# connector_final_rev01.net
KiCad netlist of a schematic drawn in EAGLE
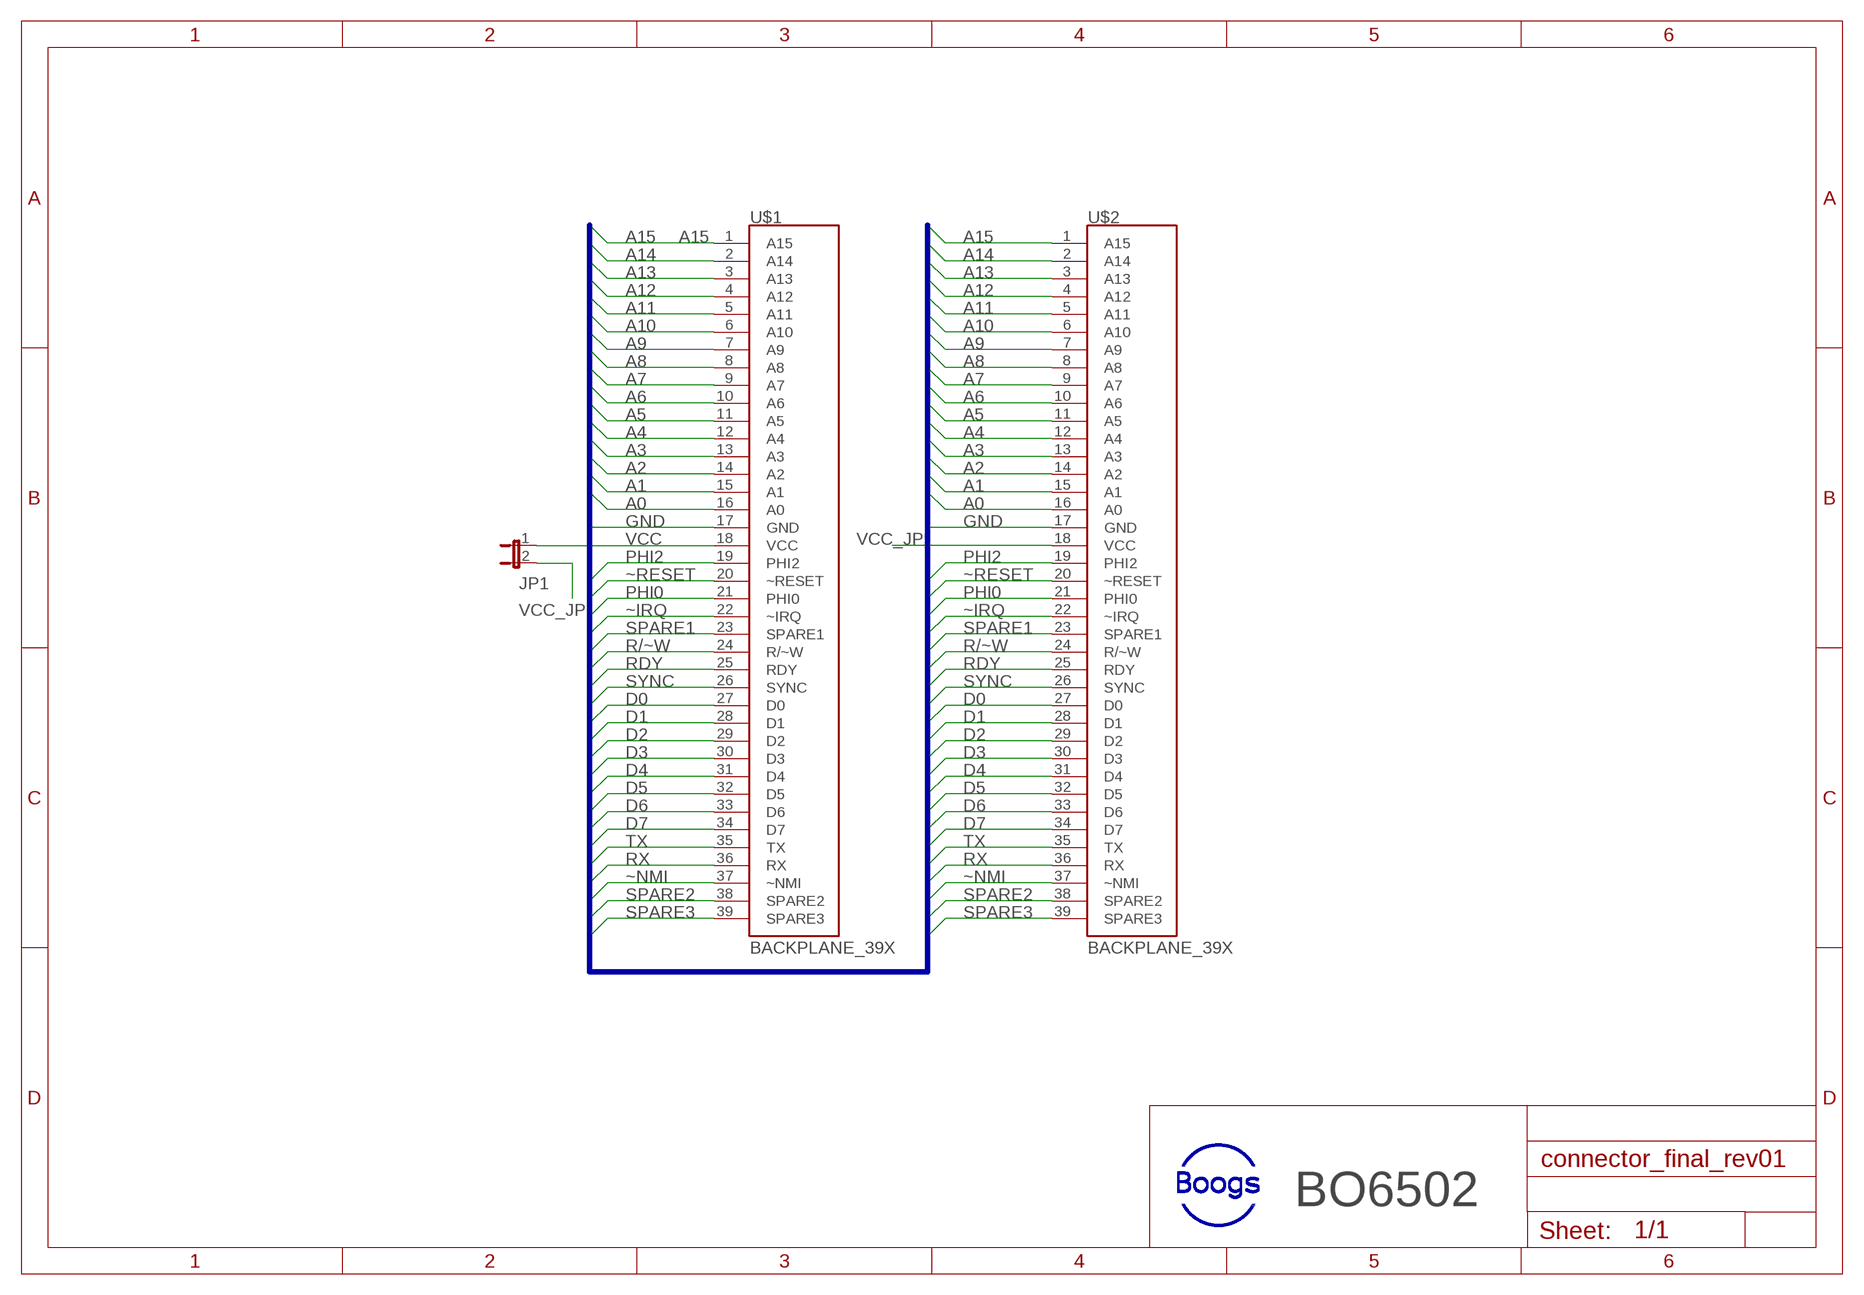
[diagram p0: schematic, sheet 1]

(export (version "E")
  (design (tool "Eeschema 10.0.6"))
  (components
    (comp (ref "JP1")
      (value "JP1E")
      (footprint "eagle-import:JP1")
      (libsource (lib "eagle-import") (part "JP1E"))
    )
    (comp (ref "U$1")
      (value "BACKPLANE_39X")
      (footprint "eagle-import:BP_39X")
      (fields (field (name "A15") "A15"))
      (libsource (lib "eagle-import") (part "BACKPLANE_39X"))
    )
    (comp (ref "U$2")
      (value "BACKPLANE_39X")
      (footprint "eagle-import:BP_39X")
      (libsource (lib "eagle-import") (part "BACKPLANE_39X"))
    )
  )
  (nets
    (net (code "1") (name "/A0") (class "Default")
      (node (ref "U$1") (pin "16") (pinfunction "A0_16") (pintype "bidirectional"))
      (node (ref "U$2") (pin "16") (pinfunction "A0_16") (pintype "bidirectional"))
    )
    (net (code "2") (name "/A1") (class "Default")
      (node (ref "U$1") (pin "15") (pinfunction "A1_15") (pintype "bidirectional"))
      (node (ref "U$2") (pin "15") (pinfunction "A1_15") (pintype "bidirectional"))
    )
    (net (code "3") (name "/A2") (class "Default")
      (node (ref "U$1") (pin "14") (pinfunction "A2_14") (pintype "bidirectional"))
      (node (ref "U$2") (pin "14") (pinfunction "A2_14") (pintype "bidirectional"))
    )
    (net (code "4") (name "/A3") (class "Default")
      (node (ref "U$1") (pin "13") (pinfunction "A3_13") (pintype "bidirectional"))
      (node (ref "U$2") (pin "13") (pinfunction "A3_13") (pintype "bidirectional"))
    )
    (net (code "5") (name "/A4") (class "Default")
      (node (ref "U$1") (pin "12") (pinfunction "A4_12") (pintype "bidirectional"))
      (node (ref "U$2") (pin "12") (pinfunction "A4_12") (pintype "bidirectional"))
    )
    (net (code "6") (name "/A5") (class "Default")
      (node (ref "U$1") (pin "11") (pinfunction "A5_11") (pintype "bidirectional"))
      (node (ref "U$2") (pin "11") (pinfunction "A5_11") (pintype "bidirectional"))
    )
    (net (code "7") (name "/A6") (class "Default")
      (node (ref "U$1") (pin "10") (pinfunction "A6_10") (pintype "bidirectional"))
      (node (ref "U$2") (pin "10") (pinfunction "A6_10") (pintype "bidirectional"))
    )
    (net (code "8") (name "/A7") (class "Default")
      (node (ref "U$1") (pin "9") (pinfunction "A7_9") (pintype "bidirectional"))
      (node (ref "U$2") (pin "9") (pinfunction "A7_9") (pintype "bidirectional"))
    )
    (net (code "9") (name "/A8") (class "Default")
      (node (ref "U$1") (pin "8") (pinfunction "A8_8") (pintype "bidirectional"))
      (node (ref "U$2") (pin "8") (pinfunction "A8_8") (pintype "bidirectional"))
    )
    (net (code "10") (name "/A9") (class "Default")
      (node (ref "U$1") (pin "7") (pinfunction "A9_7") (pintype "bidirectional"))
      (node (ref "U$2") (pin "7") (pinfunction "A9_7") (pintype "bidirectional"))
    )
    (net (code "11") (name "/A10") (class "Default")
      (node (ref "U$1") (pin "6") (pinfunction "A10_6") (pintype "bidirectional"))
      (node (ref "U$2") (pin "6") (pinfunction "A10_6") (pintype "bidirectional"))
    )
    (net (code "12") (name "/A11") (class "Default")
      (node (ref "U$1") (pin "5") (pinfunction "A11_5") (pintype "bidirectional"))
      (node (ref "U$2") (pin "5") (pinfunction "A11_5") (pintype "bidirectional"))
    )
    (net (code "13") (name "/A12") (class "Default")
      (node (ref "U$1") (pin "4") (pinfunction "A12_4") (pintype "bidirectional"))
      (node (ref "U$2") (pin "4") (pinfunction "A12_4") (pintype "bidirectional"))
    )
    (net (code "14") (name "/A13") (class "Default")
      (node (ref "U$1") (pin "3") (pinfunction "A13_3") (pintype "bidirectional"))
      (node (ref "U$2") (pin "3") (pinfunction "A13_3") (pintype "bidirectional"))
    )
    (net (code "15") (name "/A14") (class "Default")
      (node (ref "U$1") (pin "2") (pinfunction "A14_2") (pintype "bidirectional"))
      (node (ref "U$2") (pin "2") (pinfunction "A14_2") (pintype "bidirectional"))
    )
    (net (code "16") (name "/A15") (class "Default")
      (node (ref "U$1") (pin "1") (pinfunction "A15_1") (pintype "bidirectional"))
      (node (ref "U$2") (pin "1") (pinfunction "A15_1") (pintype "bidirectional"))
    )
    (net (code "17") (name "/D0") (class "Default")
      (node (ref "U$1") (pin "27") (pinfunction "D0_27") (pintype "bidirectional"))
      (node (ref "U$2") (pin "27") (pinfunction "D0_27") (pintype "bidirectional"))
    )
    (net (code "18") (name "/D1") (class "Default")
      (node (ref "U$1") (pin "28") (pinfunction "D1_28") (pintype "bidirectional"))
      (node (ref "U$2") (pin "28") (pinfunction "D1_28") (pintype "bidirectional"))
    )
    (net (code "19") (name "/D2") (class "Default")
      (node (ref "U$1") (pin "29") (pinfunction "D2_29") (pintype "bidirectional"))
      (node (ref "U$2") (pin "29") (pinfunction "D2_29") (pintype "bidirectional"))
    )
    (net (code "20") (name "/D3") (class "Default")
      (node (ref "U$1") (pin "30") (pinfunction "D3_30") (pintype "bidirectional"))
      (node (ref "U$2") (pin "30") (pinfunction "D3_30") (pintype "bidirectional"))
    )
    (net (code "21") (name "/D4") (class "Default")
      (node (ref "U$1") (pin "31") (pinfunction "D4_31") (pintype "bidirectional"))
      (node (ref "U$2") (pin "31") (pinfunction "D4_31") (pintype "bidirectional"))
    )
    (net (code "22") (name "/D5") (class "Default")
      (node (ref "U$1") (pin "32") (pinfunction "D5_32") (pintype "bidirectional"))
      (node (ref "U$2") (pin "32") (pinfunction "D5_32") (pintype "bidirectional"))
    )
    (net (code "23") (name "/D6") (class "Default")
      (node (ref "U$1") (pin "33") (pinfunction "D6_33") (pintype "bidirectional"))
      (node (ref "U$2") (pin "33") (pinfunction "D6_33") (pintype "bidirectional"))
    )
    (net (code "24") (name "/D7") (class "Default")
      (node (ref "U$1") (pin "34") (pinfunction "D7_34") (pintype "bidirectional"))
      (node (ref "U$2") (pin "34") (pinfunction "D7_34") (pintype "bidirectional"))
    )
    (net (code "25") (name "/GND") (class "Default")
      (node (ref "U$1") (pin "17") (pinfunction "GND_17") (pintype "bidirectional"))
      (node (ref "U$2") (pin "17") (pinfunction "GND_17") (pintype "bidirectional"))
    )
    (net (code "26") (name "/PHI0") (class "Default")
      (node (ref "U$1") (pin "21") (pinfunction "PHI0_21") (pintype "bidirectional"))
      (node (ref "U$2") (pin "21") (pinfunction "PHI0_21") (pintype "bidirectional"))
    )
    (net (code "27") (name "/PHI2") (class "Default")
      (node (ref "U$1") (pin "19") (pinfunction "PHI2_19") (pintype "bidirectional"))
      (node (ref "U$2") (pin "19") (pinfunction "PHI2_19") (pintype "bidirectional"))
    )
    (net (code "28") (name "/RDY") (class "Default")
      (node (ref "U$1") (pin "25") (pinfunction "RDY_25") (pintype "bidirectional"))
      (node (ref "U$2") (pin "25") (pinfunction "RDY_25") (pintype "bidirectional"))
    )
    (net (code "29") (name "/RX") (class "Default")
      (node (ref "U$1") (pin "36") (pinfunction "RX_36") (pintype "bidirectional"))
      (node (ref "U$2") (pin "36") (pinfunction "RX_36") (pintype "bidirectional"))
    )
    (net (code "30") (name "/R{slash}~{W}") (class "Default")
      (node (ref "U$1") (pin "24") (pinfunction "R/~{W}_24") (pintype "bidirectional"))
      (node (ref "U$2") (pin "24") (pinfunction "R/~{W}_24") (pintype "bidirectional"))
    )
    (net (code "31") (name "/SPARE1") (class "Default")
      (node (ref "U$1") (pin "23") (pinfunction "SPARE1_23") (pintype "bidirectional"))
      (node (ref "U$2") (pin "23") (pinfunction "SPARE1_23") (pintype "bidirectional"))
    )
    (net (code "32") (name "/SPARE2") (class "Default")
      (node (ref "U$1") (pin "38") (pinfunction "SPARE2_38") (pintype "bidirectional"))
      (node (ref "U$2") (pin "38") (pinfunction "SPARE2_38") (pintype "bidirectional"))
    )
    (net (code "33") (name "/SPARE3") (class "Default")
      (node (ref "U$1") (pin "39") (pinfunction "SPARE3_39") (pintype "bidirectional"))
      (node (ref "U$2") (pin "39") (pinfunction "SPARE3_39") (pintype "bidirectional"))
    )
    (net (code "34") (name "/SYNC") (class "Default")
      (node (ref "U$1") (pin "26") (pinfunction "SYNC_26") (pintype "bidirectional"))
      (node (ref "U$2") (pin "26") (pinfunction "SYNC_26") (pintype "bidirectional"))
    )
    (net (code "35") (name "/TX") (class "Default")
      (node (ref "U$1") (pin "35") (pinfunction "TX_35") (pintype "bidirectional"))
      (node (ref "U$2") (pin "35") (pinfunction "TX_35") (pintype "bidirectional"))
    )
    (net (code "36") (name "/VCC") (class "Default")
      (node (ref "JP1") (pin "1") (pinfunction "1_1") (pintype "passive"))
      (node (ref "U$1") (pin "18") (pinfunction "VCC_18") (pintype "bidirectional"))
    )
    (net (code "37") (name "/VCC_JP") (class "Default")
      (node (ref "JP1") (pin "2") (pinfunction "2_2") (pintype "passive"))
      (node (ref "U$2") (pin "18") (pinfunction "VCC_18") (pintype "bidirectional"))
    )
    (net (code "38") (name "/~{IRQ}") (class "Default")
      (node (ref "U$1") (pin "22") (pinfunction "~{IRQ}_22") (pintype "bidirectional"))
      (node (ref "U$2") (pin "22") (pinfunction "~{IRQ}_22") (pintype "bidirectional"))
    )
    (net (code "39") (name "/~{NMI}") (class "Default")
      (node (ref "U$1") (pin "37") (pinfunction "~{NMI}_37") (pintype "bidirectional"))
      (node (ref "U$2") (pin "37") (pinfunction "~{NMI}_37") (pintype "bidirectional"))
    )
    (net (code "40") (name "/~{RESET}") (class "Default")
      (node (ref "U$1") (pin "20") (pinfunction "~{RESET}_20") (pintype "bidirectional"))
      (node (ref "U$2") (pin "20") (pinfunction "~{RESET}_20") (pintype "bidirectional"))
    )
  )
)
